# uMatrixPCB_r1.net
KiCad netlist of a schematic drawn in EAGLE
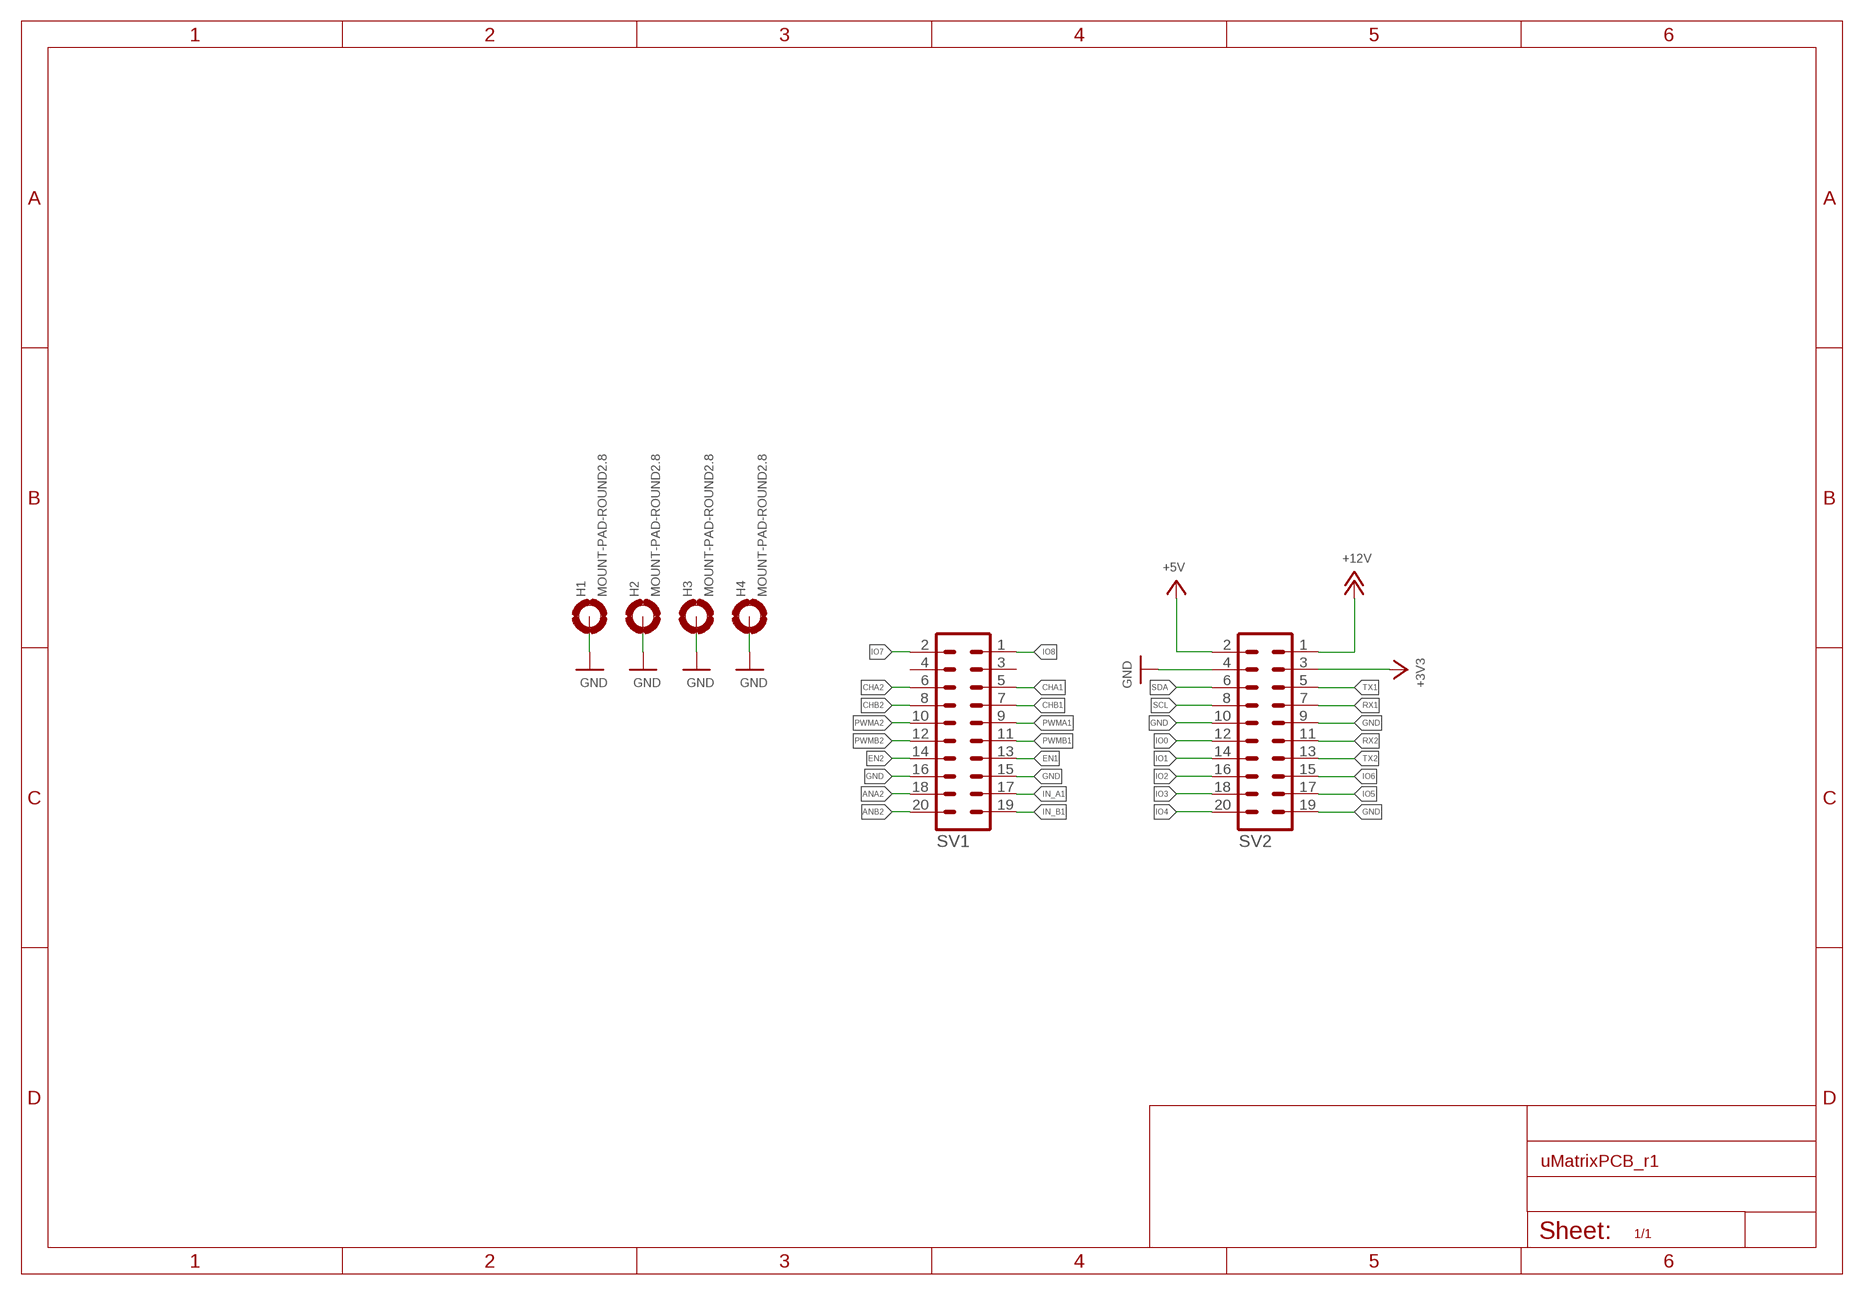
[diagram p0: schematic, sheet 1]

(export (version "E")
  (design (tool "Eeschema 10.0.6"))
  (components
    (comp (ref "H1")
      (value "MOUNT-PAD-ROUND2.8")
      (footprint "eagle-import:2,8-PAD")
      (libsource (lib "eagle-import") (part "MOUNT-PAD-ROUND2.8"))
    )
    (comp (ref "H2")
      (value "MOUNT-PAD-ROUND2.8")
      (footprint "eagle-import:2,8-PAD")
      (libsource (lib "eagle-import") (part "MOUNT-PAD-ROUND2.8"))
    )
    (comp (ref "H3")
      (value "MOUNT-PAD-ROUND2.8")
      (footprint "eagle-import:2,8-PAD")
      (libsource (lib "eagle-import") (part "MOUNT-PAD-ROUND2.8"))
    )
    (comp (ref "H4")
      (value "MOUNT-PAD-ROUND2.8")
      (footprint "eagle-import:2,8-PAD")
      (libsource (lib "eagle-import") (part "MOUNT-PAD-ROUND2.8"))
    )
    (comp (ref "SV1")
      (value "MA10-2")
      (footprint "eagle-import:MA10-2")
      (fields (field (name "OC_FARNELL") "unknown") (field (name "OC_NEWARK") "unknown"))
      (libsource (lib "eagle-import") (part "MA10-2"))
    )
    (comp (ref "SV2")
      (value "MA10-2")
      (footprint "eagle-import:MA10-2")
      (libsource (lib "eagle-import") (part "MA10-2"))
    )
  )
  (nets
    (net (code "1") (name "+3V3") (class "Default")
      (node (ref "SV2") (pin "3") (pinfunction "3_3") (pintype "passive"))
    )
    (net (code "2") (name "+5V") (class "Default")
      (node (ref "SV2") (pin "2") (pinfunction "2_2") (pintype "passive"))
    )
    (net (code "3") (name "+12V") (class "Default")
      (node (ref "SV2") (pin "1") (pinfunction "1_1") (pintype "passive"))
    )
    (net (code "4") (name "ANA2") (class "Default")
      (node (ref "SV1") (pin "18") (pinfunction "18_18") (pintype "passive"))
    )
    (net (code "5") (name "ANB2") (class "Default")
      (node (ref "SV1") (pin "20") (pinfunction "20_20") (pintype "passive"))
    )
    (net (code "6") (name "CHA1") (class "Default")
      (node (ref "SV1") (pin "5") (pinfunction "5_5") (pintype "passive"))
    )
    (net (code "7") (name "CHA2") (class "Default")
      (node (ref "SV1") (pin "6") (pinfunction "6_6") (pintype "passive"))
    )
    (net (code "8") (name "CHB1") (class "Default")
      (node (ref "SV1") (pin "7") (pinfunction "7_7") (pintype "passive"))
    )
    (net (code "9") (name "CHB2") (class "Default")
      (node (ref "SV1") (pin "8") (pinfunction "8_8") (pintype "passive"))
    )
    (net (code "10") (name "EN1") (class "Default")
      (node (ref "SV1") (pin "13") (pinfunction "13_13") (pintype "passive"))
    )
    (net (code "11") (name "EN2") (class "Default")
      (node (ref "SV1") (pin "14") (pinfunction "14_14") (pintype "passive"))
    )
    (net (code "12") (name "GND") (class "Default")
      (node (ref "H1") (pin "B2,8") (pinfunction "MOUNT_B2,8") (pintype "passive"))
      (node (ref "H2") (pin "B2,8") (pinfunction "MOUNT_B2,8") (pintype "passive"))
      (node (ref "H3") (pin "B2,8") (pinfunction "MOUNT_B2,8") (pintype "passive"))
      (node (ref "H4") (pin "B2,8") (pinfunction "MOUNT_B2,8") (pintype "passive"))
      (node (ref "SV1") (pin "15") (pinfunction "15_15") (pintype "passive"))
      (node (ref "SV1") (pin "16") (pinfunction "16_16") (pintype "passive"))
      (node (ref "SV2") (pin "10") (pinfunction "10_10") (pintype "passive"))
      (node (ref "SV2") (pin "19") (pinfunction "19_19") (pintype "passive"))
      (node (ref "SV2") (pin "4") (pinfunction "4_4") (pintype "passive"))
      (node (ref "SV2") (pin "9") (pinfunction "9_9") (pintype "passive"))
    )
    (net (code "13") (name "IN_A1") (class "Default")
      (node (ref "SV1") (pin "17") (pinfunction "17_17") (pintype "passive"))
    )
    (net (code "14") (name "IN_B1") (class "Default")
      (node (ref "SV1") (pin "19") (pinfunction "19_19") (pintype "passive"))
    )
    (net (code "15") (name "IO0") (class "Default")
      (node (ref "SV2") (pin "12") (pinfunction "12_12") (pintype "passive"))
    )
    (net (code "16") (name "IO1") (class "Default")
      (node (ref "SV2") (pin "14") (pinfunction "14_14") (pintype "passive"))
    )
    (net (code "17") (name "IO2") (class "Default")
      (node (ref "SV2") (pin "16") (pinfunction "16_16") (pintype "passive"))
    )
    (net (code "18") (name "IO3") (class "Default")
      (node (ref "SV2") (pin "18") (pinfunction "18_18") (pintype "passive"))
    )
    (net (code "19") (name "IO4") (class "Default")
      (node (ref "SV2") (pin "20") (pinfunction "20_20") (pintype "passive"))
    )
    (net (code "20") (name "IO5") (class "Default")
      (node (ref "SV2") (pin "17") (pinfunction "17_17") (pintype "passive"))
    )
    (net (code "21") (name "IO6") (class "Default")
      (node (ref "SV2") (pin "15") (pinfunction "15_15") (pintype "passive"))
    )
    (net (code "22") (name "IO7") (class "Default")
      (node (ref "SV1") (pin "2") (pinfunction "2_2") (pintype "passive"))
    )
    (net (code "23") (name "IO8") (class "Default")
      (node (ref "SV1") (pin "1") (pinfunction "1_1") (pintype "passive"))
    )
    (net (code "24") (name "PWMA1") (class "Default")
      (node (ref "SV1") (pin "9") (pinfunction "9_9") (pintype "passive"))
    )
    (net (code "25") (name "PWMA2") (class "Default")
      (node (ref "SV1") (pin "10") (pinfunction "10_10") (pintype "passive"))
    )
    (net (code "26") (name "PWMB1") (class "Default")
      (node (ref "SV1") (pin "11") (pinfunction "11_11") (pintype "passive"))
    )
    (net (code "27") (name "PWMB2") (class "Default")
      (node (ref "SV1") (pin "12") (pinfunction "12_12") (pintype "passive"))
    )
    (net (code "28") (name "RX1") (class "Default")
      (node (ref "SV2") (pin "7") (pinfunction "7_7") (pintype "passive"))
    )
    (net (code "29") (name "RX2") (class "Default")
      (node (ref "SV2") (pin "11") (pinfunction "11_11") (pintype "passive"))
    )
    (net (code "30") (name "SCL") (class "Default")
      (node (ref "SV2") (pin "8") (pinfunction "8_8") (pintype "passive"))
    )
    (net (code "31") (name "SDA") (class "Default")
      (node (ref "SV2") (pin "6") (pinfunction "6_6") (pintype "passive"))
    )
    (net (code "32") (name "TX1") (class "Default")
      (node (ref "SV2") (pin "5") (pinfunction "5_5") (pintype "passive"))
    )
    (net (code "33") (name "TX2") (class "Default")
      (node (ref "SV2") (pin "13") (pinfunction "13_13") (pintype "passive"))
    )
    (net (code "34") (name "unconnected-(SV1-Pad3)") (class "Default")
      (node (ref "SV1") (pin "3") (pinfunction "3_3") (pintype "passive"))
    )
    (net (code "35") (name "unconnected-(SV1-Pad4)") (class "Default")
      (node (ref "SV1") (pin "4") (pinfunction "4_4") (pintype "passive"))
    )
  )
)
